# MiniSCT-LB.net
KiCad netlist of a schematic drawn in Altium Designer
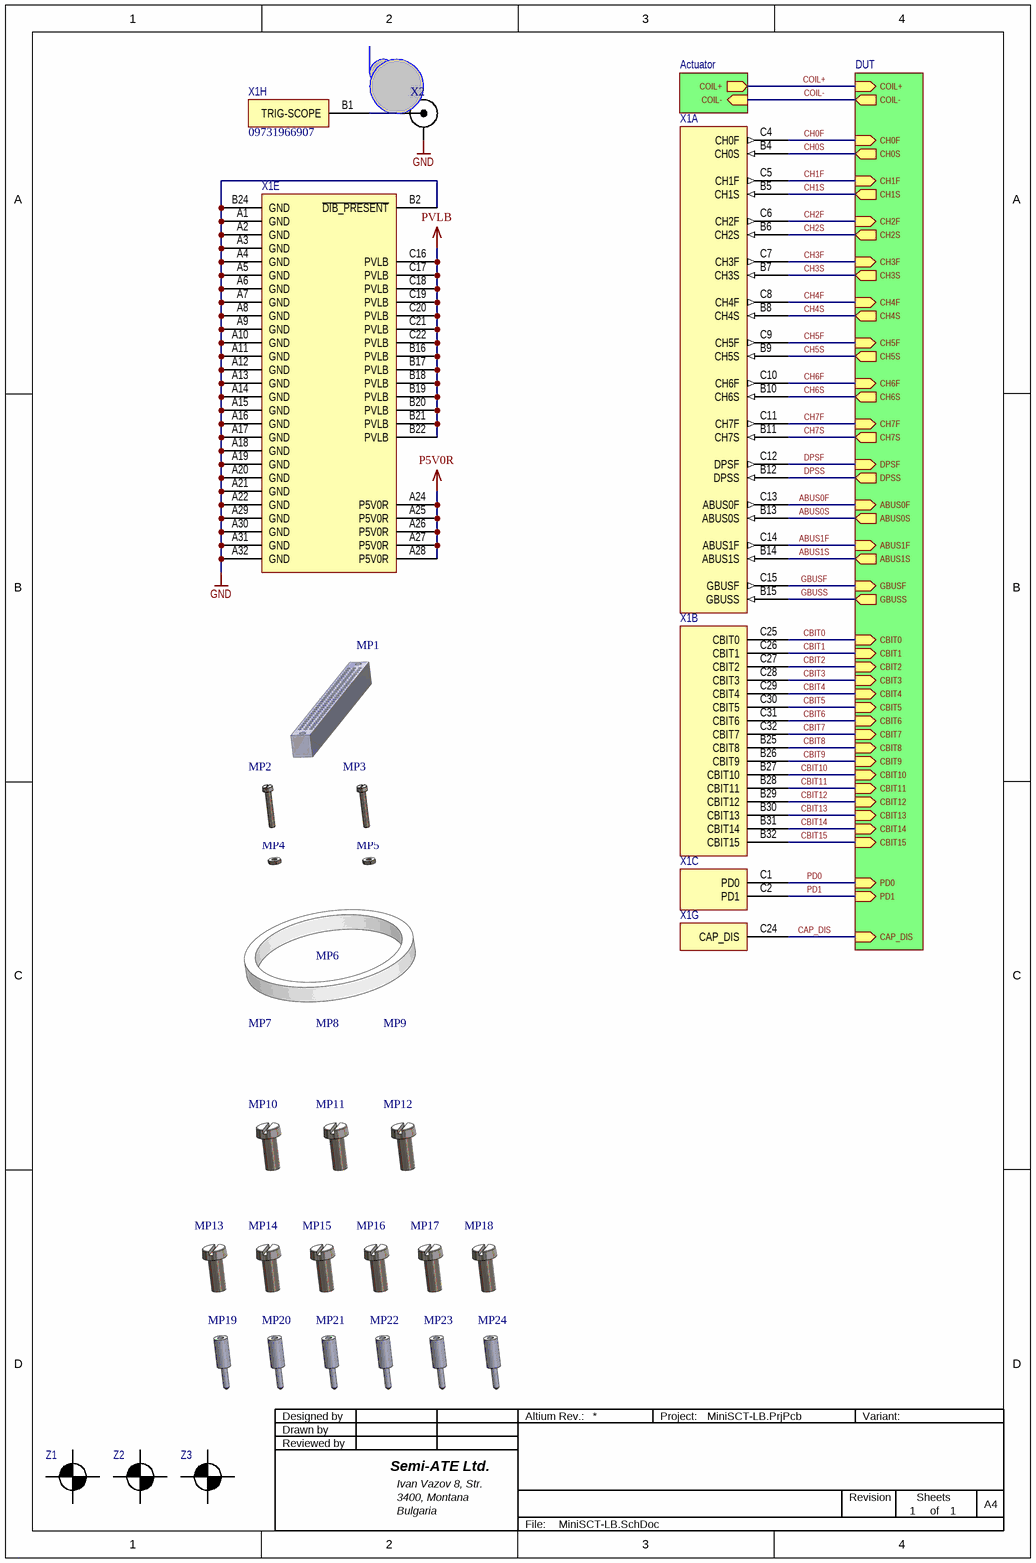
[diagram p0: MiniSCT-LB.SchDoc]

(export (version "E")
  (design (tool "Eeschema 10.0.6"))
  (components
    (comp (ref "MP1")
      (value "DIN41612 Spacer MiniSCT LB")
      (footprint "Semi-ATE:DIN41612 Spacer MiniSCT LB")
      (description "DIN41612 Spacer LoadBoard side of a MiniSCT")
      (libsource (lib "Mechanical_Parts") (part "DIN41612 Spacer MiniSCT LB"))
    )
    (comp (ref "MP2")
      (value "ISO1207 - M2.5x16")
      (footprint "Semi-ATE:ISO1207 M2.5x16")
      (description "Slotted Cheese Head Screw M2.5x16")
      (libsource (lib "Mechanical_Parts") (part "ISO1207 - M2.5x16"))
    )
    (comp (ref "MP3")
      (value "ISO1207 - M2.5x16")
      (footprint "Semi-ATE:ISO1207 M2.5x16")
      (description "Slotted Cheese Head Screw M2.5x16")
      (libsource (lib "Mechanical_Parts") (part "ISO1207 - M2.5x16"))
    )
    (comp (ref "MP4")
      (value "ISO4035 - M2.5")
      (footprint "Semi-ATE:ISO4035 - M2.5")
      (description "Hex Thin Nut Chamfered grade AB M2.5")
      (libsource (lib "Mechanical_Parts") (part "ISO4035 - M2.5"))
    )
    (comp (ref "MP5")
      (value "ISO4035 - M2.5")
      (footprint "Semi-ATE:ISO4035 - M2.5")
      (description "Hex Thin Nut Chamfered grade AB M2.5")
      (libsource (lib "Mechanical_Parts") (part "ISO4035 - M2.5"))
    )
    (comp (ref "MP6")
      (value "Thermostream Ring")
      (footprint "Semi-ATE:Thermo Stream Ring")
      (libsource (lib "Mechanical_Parts") (part "Thermostream Ring"))
    )
    (comp (ref "MP7")
      (value "Thermostream Dowel")
      (footprint "Semi-ATE:Thermo Dowel")
      (libsource (lib "Mechanical_Parts") (part "Thermostream Dowel"))
    )
    (comp (ref "MP8")
      (value "Thermostream Dowel")
      (footprint "Semi-ATE:Thermo Dowel")
      (libsource (lib "Mechanical_Parts") (part "Thermostream Dowel"))
    )
    (comp (ref "MP9")
      (value "Thermostream Dowel")
      (footprint "Semi-ATE:Thermo Dowel")
      (libsource (lib "Mechanical_Parts") (part "Thermostream Dowel"))
    )
    (comp (ref "MP10")
      (value "ISO1207 - M4x10")
      (footprint "Semi-ATE:ISO1207 M4x10")
      (description "Slotted Cheese Head Screw M4x10")
      (libsource (lib "Mechanical_Parts") (part "ISO1207 - M4x10"))
    )
    (comp (ref "MP11")
      (value "ISO1207 - M4x10")
      (footprint "Semi-ATE:ISO1207 M4x10")
      (description "Slotted Cheese Head Screw M4x10")
      (libsource (lib "Mechanical_Parts") (part "ISO1207 - M4x10"))
    )
    (comp (ref "MP12")
      (value "ISO1207 - M4x10")
      (footprint "Semi-ATE:ISO1207 M4x10")
      (description "Slotted Cheese Head Screw M4x10")
      (libsource (lib "Mechanical_Parts") (part "ISO1207 - M4x10"))
    )
    (comp (ref "MP13")
      (value "ISO1207 - M4x10")
      (footprint "Semi-ATE:ISO1207 M4x10")
      (description "Slotted Cheese Head Screw M4x10")
      (libsource (lib "Mechanical_Parts") (part "ISO1207 - M4x10"))
    )
    (comp (ref "MP14")
      (value "ISO1207 - M4x10")
      (footprint "Semi-ATE:ISO1207 M4x10")
      (description "Slotted Cheese Head Screw M4x10")
      (libsource (lib "Mechanical_Parts") (part "ISO1207 - M4x10"))
    )
    (comp (ref "MP15")
      (value "ISO1207 - M4x10")
      (footprint "Semi-ATE:ISO1207 M4x10")
      (description "Slotted Cheese Head Screw M4x10")
      (libsource (lib "Mechanical_Parts") (part "ISO1207 - M4x10"))
    )
    (comp (ref "MP16")
      (value "ISO1207 - M4x10")
      (footprint "Semi-ATE:ISO1207 M4x10")
      (description "Slotted Cheese Head Screw M4x10")
      (libsource (lib "Mechanical_Parts") (part "ISO1207 - M4x10"))
    )
    (comp (ref "MP17")
      (value "ISO1207 - M4x10")
      (footprint "Semi-ATE:ISO1207 M4x10")
      (description "Slotted Cheese Head Screw M4x10")
      (libsource (lib "Mechanical_Parts") (part "ISO1207 - M4x10"))
    )
    (comp (ref "MP18")
      (value "ISO1207 - M4x10")
      (footprint "Semi-ATE:ISO1207 M4x10")
      (description "Slotted Cheese Head Screw M4x10")
      (libsource (lib "Mechanical_Parts") (part "ISO1207 - M4x10"))
    )
    (comp (ref "MP19")
      (value "MiniSCT LB StandOff")
      (footprint "Semi-ATE:MiniSCT LB StandOff")
      (description "MiniSCT LoadBoard StandOff")
      (libsource (lib "Mechanical_Parts") (part "MiniSCT LB StandOff"))
    )
    (comp (ref "MP20")
      (value "MiniSCT LB StandOff")
      (footprint "Semi-ATE:MiniSCT LB StandOff")
      (description "MiniSCT LoadBoard StandOff")
      (libsource (lib "Mechanical_Parts") (part "MiniSCT LB StandOff"))
    )
    (comp (ref "MP21")
      (value "MiniSCT LB StandOff")
      (footprint "Semi-ATE:MiniSCT LB StandOff")
      (description "MiniSCT LoadBoard StandOff")
      (libsource (lib "Mechanical_Parts") (part "MiniSCT LB StandOff"))
    )
    (comp (ref "MP22")
      (value "MiniSCT LB StandOff")
      (footprint "Semi-ATE:MiniSCT LB StandOff")
      (description "MiniSCT LoadBoard StandOff")
      (libsource (lib "Mechanical_Parts") (part "MiniSCT LB StandOff"))
    )
    (comp (ref "MP23")
      (value "MiniSCT LB StandOff")
      (footprint "Semi-ATE:MiniSCT LB StandOff")
      (description "MiniSCT LoadBoard StandOff")
      (libsource (lib "Mechanical_Parts") (part "MiniSCT LB StandOff"))
    )
    (comp (ref "MP24")
      (value "MiniSCT LB StandOff")
      (footprint "Semi-ATE:MiniSCT LB StandOff")
      (description "MiniSCT LoadBoard StandOff")
      (libsource (lib "Mechanical_Parts") (part "MiniSCT LB StandOff"))
    )
    (comp (ref "X1")
      (value "09731966907")
      (footprint "Semi-ATE:09731966907")
      (description "96 Position Din Connector Header, Male Pins Gold or Gold-Palladium Through Hole")
      (fields (field (name "MANUFACTURER") "Harting"))
      (libsource (lib "Connections") (part "MiniSCT8"))
    )
    (comp (ref "X2")
      (value "112778")
      (footprint "Semi-ATE:112778")
      (description "CONN BNC JACK R/A 75 OHM PCB")
      (fields (field (name "MANUFACTURER") "Amphenol RF"))
      (libsource (lib "Connections") (part "CON_TH_2_F_90_BNC"))
    )
    (comp (ref "Z1")
      (value "Fiducial")
      (footprint "Semi-ATE:Fiducial Cross")
      (description "Assembly AOI")
      (libsource (lib "Miscellaneous") (part "Fiducial"))
    )
    (comp (ref "Z2")
      (value "Fiducial")
      (footprint "Semi-ATE:Fiducial Point")
      (description "Assembly AOI")
      (libsource (lib "Miscellaneous") (part "Fiducial"))
    )
    (comp (ref "Z3")
      (value "Fiducial")
      (footprint "Semi-ATE:Fiducial Cross")
      (description "Assembly AOI")
      (libsource (lib "Miscellaneous") (part "Fiducial"))
    )
  )
  (nets
    (net (code "1") (name "/ABUS0F") (class "Default")
      (node (ref "X1") (pin "C13") (pinfunction "ABUS0F_C13") (pintype "output"))
    )
    (net (code "2") (name "/ABUS0S") (class "Default")
      (node (ref "X1") (pin "B13") (pinfunction "ABUS0S_B13") (pintype "input"))
    )
    (net (code "3") (name "/ABUS1F") (class "Default")
      (node (ref "X1") (pin "C14") (pinfunction "ABUS1F_C14") (pintype "output"))
    )
    (net (code "4") (name "/ABUS1S") (class "Default")
      (node (ref "X1") (pin "B14") (pinfunction "ABUS1S_B14") (pintype "input"))
    )
    (net (code "5") (name "/CAP_DIS") (class "Default")
      (node (ref "X1") (pin "C24") (pinfunction "CAP_DIS_C24") (pintype "passive"))
    )
    (net (code "6") (name "/CBIT0") (class "Default")
      (node (ref "X1") (pin "C25") (pinfunction "CBIT0_C25") (pintype "open_collector"))
    )
    (net (code "7") (name "/CBIT1") (class "Default")
      (node (ref "X1") (pin "C26") (pinfunction "CBIT1_C26") (pintype "open_collector"))
    )
    (net (code "8") (name "/CBIT2") (class "Default")
      (node (ref "X1") (pin "C27") (pinfunction "CBIT2_C27") (pintype "open_collector"))
    )
    (net (code "9") (name "/CBIT3") (class "Default")
      (node (ref "X1") (pin "C28") (pinfunction "CBIT3_C28") (pintype "open_collector"))
    )
    (net (code "10") (name "/CBIT4") (class "Default")
      (node (ref "X1") (pin "C29") (pinfunction "CBIT4_C29") (pintype "open_collector"))
    )
    (net (code "11") (name "/CBIT5") (class "Default")
      (node (ref "X1") (pin "C30") (pinfunction "CBIT5_C30") (pintype "open_collector"))
    )
    (net (code "12") (name "/CBIT6") (class "Default")
      (node (ref "X1") (pin "C31") (pinfunction "CBIT6_C31") (pintype "open_collector"))
    )
    (net (code "13") (name "/CBIT7") (class "Default")
      (node (ref "X1") (pin "C32") (pinfunction "CBIT7_C32") (pintype "open_collector"))
    )
    (net (code "14") (name "/CBIT8") (class "Default")
      (node (ref "X1") (pin "B25") (pinfunction "CBIT8_B25") (pintype "open_collector"))
    )
    (net (code "15") (name "/CBIT9") (class "Default")
      (node (ref "X1") (pin "B26") (pinfunction "CBIT9_B26") (pintype "open_collector"))
    )
    (net (code "16") (name "/CBIT10") (class "Default")
      (node (ref "X1") (pin "B27") (pinfunction "CBIT10_B27") (pintype "open_collector"))
    )
    (net (code "17") (name "/CBIT11") (class "Default")
      (node (ref "X1") (pin "B28") (pinfunction "CBIT11_B28") (pintype "open_collector"))
    )
    (net (code "18") (name "/CBIT12") (class "Default")
      (node (ref "X1") (pin "B29") (pinfunction "CBIT12_B29") (pintype "open_collector"))
    )
    (net (code "19") (name "/CBIT13") (class "Default")
      (node (ref "X1") (pin "B30") (pinfunction "CBIT13_B30") (pintype "open_collector"))
    )
    (net (code "20") (name "/CBIT14") (class "Default")
      (node (ref "X1") (pin "B31") (pinfunction "CBIT14_B31") (pintype "open_collector"))
    )
    (net (code "21") (name "/CBIT15") (class "Default")
      (node (ref "X1") (pin "B32") (pinfunction "CBIT15_B32") (pintype "open_collector"))
    )
    (net (code "22") (name "/CH0F") (class "Default")
      (node (ref "X1") (pin "C4") (pinfunction "CH0F_C4") (pintype "output"))
    )
    (net (code "23") (name "/CH0S") (class "Default")
      (node (ref "X1") (pin "B4") (pinfunction "CH0S_B4") (pintype "input"))
    )
    (net (code "24") (name "/CH1F") (class "Default")
      (node (ref "X1") (pin "C5") (pinfunction "CH1F_C5") (pintype "output"))
    )
    (net (code "25") (name "/CH1S") (class "Default")
      (node (ref "X1") (pin "B5") (pinfunction "CH1S_B5") (pintype "input"))
    )
    (net (code "26") (name "/CH2F") (class "Default")
      (node (ref "X1") (pin "C6") (pinfunction "CH2F_C6") (pintype "output"))
    )
    (net (code "27") (name "/CH2S") (class "Default")
      (node (ref "X1") (pin "B6") (pinfunction "CH2S_B6") (pintype "input"))
    )
    (net (code "28") (name "/CH3F") (class "Default")
      (node (ref "X1") (pin "C7") (pinfunction "CH3F_C7") (pintype "output"))
    )
    (net (code "29") (name "/CH3S") (class "Default")
      (node (ref "X1") (pin "B7") (pinfunction "CH3S_B7") (pintype "input"))
    )
    (net (code "30") (name "/CH4F") (class "Default")
      (node (ref "X1") (pin "C8") (pinfunction "CH4F_C8") (pintype "output"))
    )
    (net (code "31") (name "/CH4S") (class "Default")
      (node (ref "X1") (pin "B8") (pinfunction "CH4S_B8") (pintype "input"))
    )
    (net (code "32") (name "/CH5F") (class "Default")
      (node (ref "X1") (pin "C9") (pinfunction "CH5F_C9") (pintype "output"))
    )
    (net (code "33") (name "/CH5S") (class "Default")
      (node (ref "X1") (pin "B9") (pinfunction "CH5S_B9") (pintype "input"))
    )
    (net (code "34") (name "/CH6F") (class "Default")
      (node (ref "X1") (pin "C10") (pinfunction "CH6F_C10") (pintype "output"))
    )
    (net (code "35") (name "/CH6S") (class "Default")
      (node (ref "X1") (pin "B10") (pinfunction "CH6S_B10") (pintype "input"))
    )
    (net (code "36") (name "/CH7F") (class "Default")
      (node (ref "X1") (pin "C11") (pinfunction "CH7F_C11") (pintype "output"))
    )
    (net (code "37") (name "/CH7S") (class "Default")
      (node (ref "X1") (pin "B11") (pinfunction "CH7S_B11") (pintype "input"))
    )
    (net (code "40") (name "/DPSF") (class "Default")
      (node (ref "X1") (pin "C12") (pinfunction "DPSF_C12") (pintype "output"))
    )
    (net (code "41") (name "/DPSS") (class "Default")
      (node (ref "X1") (pin "B12") (pinfunction "DPSS_B12") (pintype "input"))
    )
    (net (code "42") (name "/GBUSF") (class "Default")
      (node (ref "X1") (pin "C15") (pinfunction "GBUSF_C15") (pintype "output"))
    )
    (net (code "43") (name "/GBUSS") (class "Default")
      (node (ref "X1") (pin "B15") (pinfunction "GBUSS_B15") (pintype "input"))
    )
    (net (code "44") (name "/PD0") (class "Default")
      (node (ref "X1") (pin "C1") (pinfunction "PD0_C1") (pintype "passive"))
    )
    (net (code "45") (name "/PD1") (class "Default")
      (node (ref "X1") (pin "C2") (pinfunction "PD1_C2") (pintype "passive"))
    )
    (net (code "46") (name "GND") (class "Default")
      (node (ref "X1") (pin "A1") (pinfunction "GND_A1") (pintype "passive"))
      (node (ref "X1") (pin "A10") (pinfunction "GND_A10") (pintype "passive"))
      (node (ref "X1") (pin "A11") (pinfunction "GND_A11") (pintype "passive"))
      (node (ref "X1") (pin "A12") (pinfunction "GND_A12") (pintype "passive"))
      (node (ref "X1") (pin "A13") (pinfunction "GND_A13") (pintype "passive"))
      (node (ref "X1") (pin "A14") (pinfunction "GND_A14") (pintype "passive"))
      (node (ref "X1") (pin "A15") (pinfunction "GND_A15") (pintype "passive"))
      (node (ref "X1") (pin "A16") (pinfunction "GND_A16") (pintype "passive"))
      (node (ref "X1") (pin "A17") (pinfunction "GND_A17") (pintype "passive"))
      (node (ref "X1") (pin "A18") (pinfunction "GND_A18") (pintype "passive"))
      (node (ref "X1") (pin "A19") (pinfunction "GND_A19") (pintype "passive"))
      (node (ref "X1") (pin "A2") (pinfunction "GND_A2") (pintype "passive"))
      (node (ref "X1") (pin "A20") (pinfunction "GND_A20") (pintype "passive"))
      (node (ref "X1") (pin "A21") (pinfunction "GND_A21") (pintype "passive"))
      (node (ref "X1") (pin "A22") (pinfunction "GND_A22") (pintype "passive"))
      (node (ref "X1") (pin "A29") (pinfunction "GND_A29") (pintype "passive"))
      (node (ref "X1") (pin "A3") (pinfunction "GND_A3") (pintype "passive"))
      (node (ref "X1") (pin "A30") (pinfunction "GND_A30") (pintype "passive"))
      (node (ref "X1") (pin "A31") (pinfunction "GND_A31") (pintype "passive"))
      (node (ref "X1") (pin "A32") (pinfunction "GND_A32") (pintype "passive"))
      (node (ref "X1") (pin "A4") (pinfunction "GND_A4") (pintype "passive"))
      (node (ref "X1") (pin "A5") (pinfunction "GND_A5") (pintype "passive"))
      (node (ref "X1") (pin "A6") (pinfunction "GND_A6") (pintype "passive"))
      (node (ref "X1") (pin "A7") (pinfunction "GND_A7") (pintype "passive"))
      (node (ref "X1") (pin "A8") (pinfunction "GND_A8") (pintype "passive"))
      (node (ref "X1") (pin "A9") (pinfunction "GND_A9") (pintype "passive"))
      (node (ref "X1") (pin "B2") (pinfunction "~{DIB_PRESENT}_B2") (pintype "passive"))
      (node (ref "X1") (pin "B24") (pinfunction "GND_B24") (pintype "passive"))
      (node (ref "X2") (pin "0") (pinfunction "Shield_0") (pintype "passive"))
    )
    (net (code "47") (name "Net-(X1H-TRIG-SCOPE)") (class "Default")
      (node (ref "X1") (pin "B1") (pinfunction "TRIG-SCOPE_B1") (pintype "passive"))
      (node (ref "X2") (pin "1") (pinfunction "Signal_1") (pintype "passive"))
    )
    (net (code "48") (name "P5V0R") (class "Default")
      (node (ref "X1") (pin "A24") (pinfunction "P5V0R_A24") (pintype "passive"))
      (node (ref "X1") (pin "A25") (pinfunction "P5V0R_A25") (pintype "passive"))
      (node (ref "X1") (pin "A26") (pinfunction "P5V0R_A26") (pintype "passive"))
      (node (ref "X1") (pin "A27") (pinfunction "P5V0R_A27") (pintype "passive"))
      (node (ref "X1") (pin "A28") (pinfunction "P5V0R_A28") (pintype "passive"))
    )
    (net (code "49") (name "PVLB") (class "Default")
      (node (ref "X1") (pin "B16") (pinfunction "PVLB_B16") (pintype "passive"))
      (node (ref "X1") (pin "B17") (pinfunction "PVLB_B17") (pintype "passive"))
      (node (ref "X1") (pin "B18") (pinfunction "PVLB_B18") (pintype "passive"))
      (node (ref "X1") (pin "B19") (pinfunction "PVLB_B19") (pintype "passive"))
      (node (ref "X1") (pin "B20") (pinfunction "PVLB_B20") (pintype "passive"))
      (node (ref "X1") (pin "B21") (pinfunction "PVLB_B21") (pintype "passive"))
      (node (ref "X1") (pin "B22") (pinfunction "PVLB_B22") (pintype "passive"))
      (node (ref "X1") (pin "C16") (pinfunction "PVLB_C16") (pintype "passive"))
      (node (ref "X1") (pin "C17") (pinfunction "PVLB_C17") (pintype "passive"))
      (node (ref "X1") (pin "C18") (pinfunction "PVLB_C18") (pintype "passive"))
      (node (ref "X1") (pin "C19") (pinfunction "PVLB_C19") (pintype "passive"))
      (node (ref "X1") (pin "C20") (pinfunction "PVLB_C20") (pintype "passive"))
      (node (ref "X1") (pin "C21") (pinfunction "PVLB_C21") (pintype "passive"))
      (node (ref "X1") (pin "C22") (pinfunction "PVLB_C22") (pintype "passive"))
    )
  )
)
